# diskohedron4w_revb.net
KiCad netlist of a schematic drawn in EAGLE
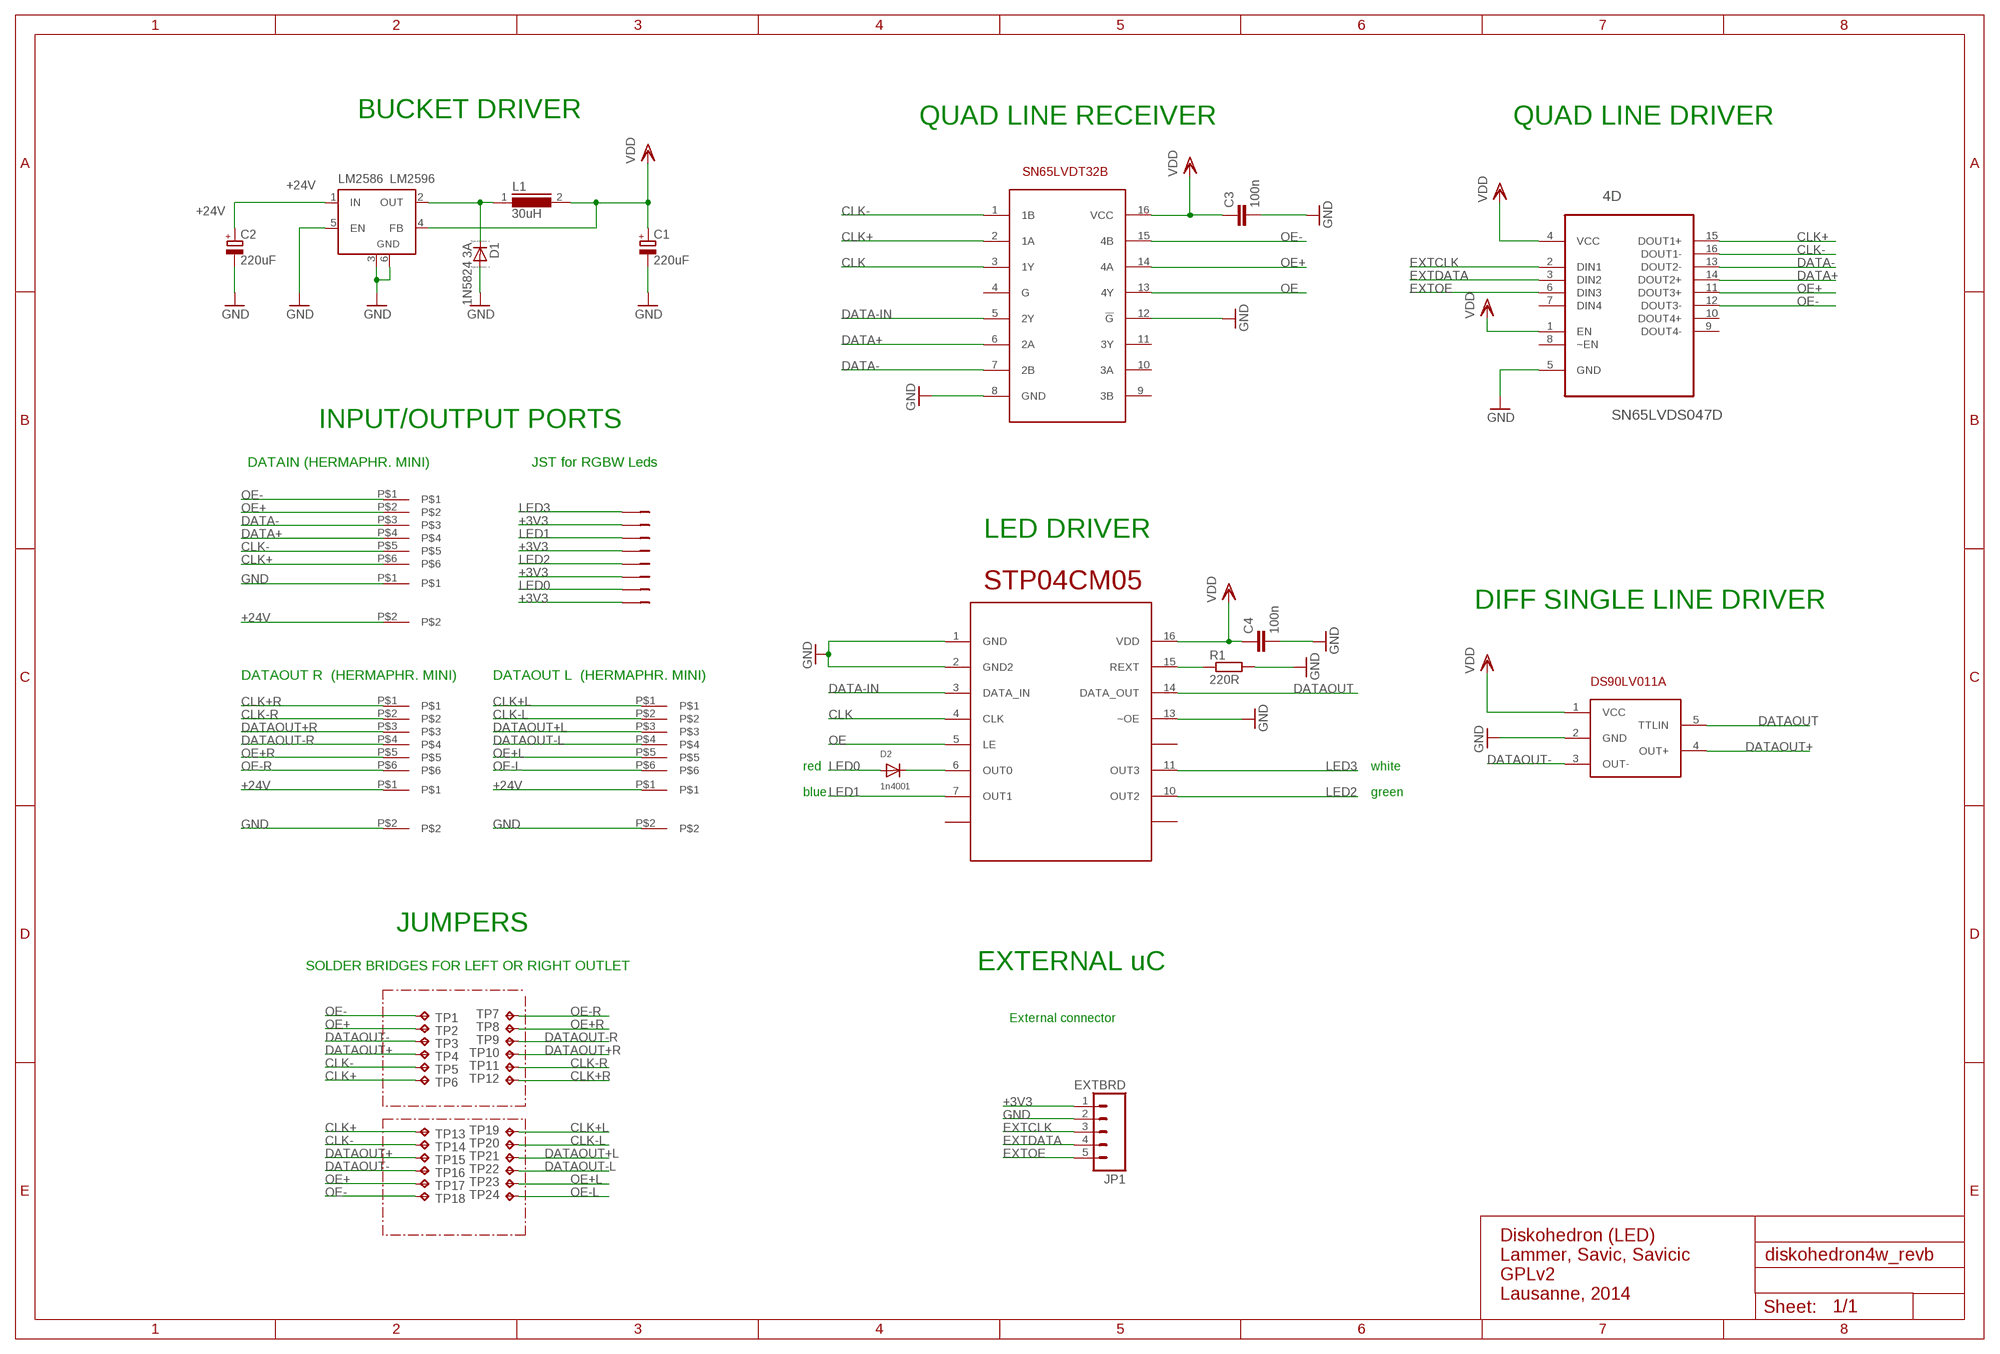
[diagram p0: schematic, sheet 1]

(export (version "E")
  (design (tool "Eeschema 10.0.6"))
  (components
    (comp (ref "1D")
      (value "DS90LV011A")
      (footprint "eagle-import:SOT23-5")
      (libsource (lib "eagle-import") (part "DS90LV011A"))
    )
    (comp (ref "4D")
      (value "SN65LVDS047D")
      (footprint "eagle-import:SOIC127P600X175-16N")
      (libsource (lib "eagle-import") (part "SN65LVDS047D"))
    )
    (comp (ref "4R")
      (value "SN65LVDST32")
      (footprint "eagle-import:SOIC16")
      (libsource (lib "eagle-import") (part "SN65LVDST32"))
    )
    (comp (ref "C1")
      (value "220uF")
      (footprint "eagle-import:175TMP-0810")
      (libsource (lib "eagle-import") (part "CPOL-EU175TMP-0810"))
    )
    (comp (ref "C2")
      (value "220uF")
      (footprint "eagle-import:175TMP-0810")
      (libsource (lib "eagle-import") (part "CPOL-EU175TMP-0810"))
    )
    (comp (ref "C3")
      (value "100n")
      (footprint "eagle-import:C0805")
      (libsource (lib "eagle-import") (part "C-EUC0805"))
    )
    (comp (ref "C4")
      (value "100n")
      (footprint "eagle-import:C0805")
      (libsource (lib "eagle-import") (part "C-EUC0805"))
    )
    (comp (ref "D1")
      (value "1N5824 3A")
      (footprint "eagle-import:DIODE_SMC")
      (libsource (lib "eagle-import") (part "DIODE_E-SMC"))
    )
    (comp (ref "D2")
      (value "1n4001")
      (footprint "eagle-import:SMADIODE")
      (libsource (lib "eagle-import") (part "DIODESMA"))
    )
    (comp (ref "IN1")
      (value "HERMAPHRODITMINI6PIN")
      (footprint "eagle-import:HERMAPHRODITMINI6PIN")
      (libsource (lib "eagle-import") (part "HERMAPHRODITMINI6PIN"))
    )
    (comp (ref "JP1")
      (value "EXTBRD")
      (footprint "eagle-import:1X05")
      (libsource (lib "eagle-import") (part "M05PTH"))
    )
    (comp (ref "JST")
      (value "8PIN-ZH")
      (footprint "eagle-import:B8B-ZH")
      (libsource (lib "eagle-import") (part "8PIN-ZH"))
    )
    (comp (ref "L1")
      (value "30uH")
      (footprint "eagle-import:DR127")
      (libsource (lib "eagle-import") (part "DR127"))
    )
    (comp (ref "LM2586")
      (value "LM2596")
      (footprint "eagle-import:TO263-5")
      (libsource (lib "eagle-import") (part "LM2596S"))
    )
    (comp (ref "OUT-L")
      (value "HERMAPHRODITMINI6PIN")
      (footprint "eagle-import:HERMAPHRODITMINI6PIN")
      (libsource (lib "eagle-import") (part "HERMAPHRODITMINI6PIN"))
    )
    (comp (ref "OUT-R")
      (value "HERMAPHRODITMINI6PIN")
      (footprint "eagle-import:HERMAPHRODITMINI6PIN")
      (libsource (lib "eagle-import") (part "HERMAPHRODITMINI6PIN"))
    )
    (comp (ref "R1")
      (value "220R")
      (footprint "eagle-import:M0805")
      (libsource (lib "eagle-import") (part "R-EU_M0805"))
    )
    (comp (ref "STP04")
      (value "STP04CM05")
      (footprint "eagle-import:TSSOP16")
      (libsource (lib "eagle-import") (part "STP04CM05"))
    )
    (comp (ref "TP1")
      (value "TPTP12SQ")
      (footprint "eagle-import:TP12SQ")
      (libsource (lib "eagle-import") (part "TPTP12SQ"))
    )
    (comp (ref "TP2")
      (value "TPTP12SQ")
      (footprint "eagle-import:TP12SQ")
      (libsource (lib "eagle-import") (part "TPTP12SQ"))
    )
    (comp (ref "TP3")
      (value "TPTP12SQ")
      (footprint "eagle-import:TP12SQ")
      (libsource (lib "eagle-import") (part "TPTP12SQ"))
    )
    (comp (ref "TP4")
      (value "TPTP12SQ")
      (footprint "eagle-import:TP12SQ")
      (libsource (lib "eagle-import") (part "TPTP12SQ"))
    )
    (comp (ref "TP5")
      (value "TPTP12SQ")
      (footprint "eagle-import:TP12SQ")
      (libsource (lib "eagle-import") (part "TPTP12SQ"))
    )
    (comp (ref "TP6")
      (value "TPTP12SQ")
      (footprint "eagle-import:TP12SQ")
      (libsource (lib "eagle-import") (part "TPTP12SQ"))
    )
    (comp (ref "TP7")
      (value "TPTP12SQ")
      (footprint "eagle-import:TP12SQ")
      (libsource (lib "eagle-import") (part "TPTP12SQ"))
    )
    (comp (ref "TP8")
      (value "TPTP12SQ")
      (footprint "eagle-import:TP12SQ")
      (libsource (lib "eagle-import") (part "TPTP12SQ"))
    )
    (comp (ref "TP9")
      (value "TPTP12SQ")
      (footprint "eagle-import:TP12SQ")
      (libsource (lib "eagle-import") (part "TPTP12SQ"))
    )
    (comp (ref "TP10")
      (value "TPTP12SQ")
      (footprint "eagle-import:TP12SQ")
      (libsource (lib "eagle-import") (part "TPTP12SQ"))
    )
    (comp (ref "TP11")
      (value "TPTP12SQ")
      (footprint "eagle-import:TP12SQ")
      (libsource (lib "eagle-import") (part "TPTP12SQ"))
    )
    (comp (ref "TP12")
      (value "TPTP12SQ")
      (footprint "eagle-import:TP12SQ")
      (libsource (lib "eagle-import") (part "TPTP12SQ"))
    )
    (comp (ref "TP13")
      (value "TPTP12SQ")
      (footprint "eagle-import:TP12SQ")
      (libsource (lib "eagle-import") (part "TPTP12SQ"))
    )
    (comp (ref "TP14")
      (value "TPTP12SQ")
      (footprint "eagle-import:TP12SQ")
      (libsource (lib "eagle-import") (part "TPTP12SQ"))
    )
    (comp (ref "TP15")
      (value "TPTP12SQ")
      (footprint "eagle-import:TP12SQ")
      (libsource (lib "eagle-import") (part "TPTP12SQ"))
    )
    (comp (ref "TP16")
      (value "TPTP12SQ")
      (footprint "eagle-import:TP12SQ")
      (libsource (lib "eagle-import") (part "TPTP12SQ"))
    )
    (comp (ref "TP17")
      (value "TPTP12SQ")
      (footprint "eagle-import:TP12SQ")
      (libsource (lib "eagle-import") (part "TPTP12SQ"))
    )
    (comp (ref "TP18")
      (value "TPTP12SQ")
      (footprint "eagle-import:TP12SQ")
      (libsource (lib "eagle-import") (part "TPTP12SQ"))
    )
    (comp (ref "TP19")
      (value "TPTP12SQ")
      (footprint "eagle-import:TP12SQ")
      (libsource (lib "eagle-import") (part "TPTP12SQ"))
    )
    (comp (ref "TP20")
      (value "TPTP12SQ")
      (footprint "eagle-import:TP12SQ")
      (libsource (lib "eagle-import") (part "TPTP12SQ"))
    )
    (comp (ref "TP21")
      (value "TPTP12SQ")
      (footprint "eagle-import:TP12SQ")
      (libsource (lib "eagle-import") (part "TPTP12SQ"))
    )
    (comp (ref "TP22")
      (value "TPTP12SQ")
      (footprint "eagle-import:TP12SQ")
      (libsource (lib "eagle-import") (part "TPTP12SQ"))
    )
    (comp (ref "TP23")
      (value "TPTP12SQ")
      (footprint "eagle-import:TP12SQ")
      (libsource (lib "eagle-import") (part "TPTP12SQ"))
    )
    (comp (ref "TP24")
      (value "TPTP12SQ")
      (footprint "eagle-import:TP12SQ")
      (libsource (lib "eagle-import") (part "TPTP12SQ"))
    )
    (comp (ref "U$6")
      (value "HERMAPHRODIT2PIN")
      (footprint "eagle-import:HERMAPHRODIT2PIN")
      (libsource (lib "eagle-import") (part "HERMAPHRODIT2PIN"))
    )
    (comp (ref "U$7")
      (value "HERMAPHRODIT2PIN")
      (footprint "eagle-import:HERMAPHRODIT2PIN")
      (libsource (lib "eagle-import") (part "HERMAPHRODIT2PIN"))
    )
    (comp (ref "U$12")
      (value "HERMAPHRODIT2PIN")
      (footprint "eagle-import:HERMAPHRODIT2PIN")
      (libsource (lib "eagle-import") (part "HERMAPHRODIT2PIN"))
    )
  )
  (nets
    (net (code "1") (name "/+24V") (class "Default")
      (node (ref "C2") (pin "+") (pinfunction "+_+") (pintype "passive"))
      (node (ref "LM2586") (pin "1") (pinfunction "IN_1") (pintype "input"))
      (node (ref "U$12") (pin "P$1") (pinfunction "P$1_P$1") (pintype "bidirectional"))
      (node (ref "U$6") (pin "P$1") (pinfunction "P$1_P$1") (pintype "bidirectional"))
      (node (ref "U$7") (pin "P$2") (pinfunction "P$2_P$2") (pintype "bidirectional"))
    )
    (net (code "2") (name "/CLK") (class "Default")
      (node (ref "4R") (pin "3") (pinfunction "1Y_3") (pintype "bidirectional"))
      (node (ref "STP04") (pin "4") (pinfunction "CLK_4") (pintype "bidirectional"))
    )
    (net (code "3") (name "/CLK+") (class "Default")
      (node (ref "4D") (pin "15") (pinfunction "DOUT1+_15") (pintype "output"))
      (node (ref "4R") (pin "2") (pinfunction "1A_2") (pintype "bidirectional"))
      (node (ref "IN1") (pin "P$6") (pinfunction "P$6_P$6") (pintype "bidirectional"))
      (node (ref "TP13") (pin "TP") (pinfunction "TP_TP") (pintype "input"))
      (node (ref "TP6") (pin "TP") (pinfunction "TP_TP") (pintype "input"))
    )
    (net (code "4") (name "/CLK+L") (class "Default")
      (node (ref "OUT-L") (pin "P$1") (pinfunction "P$1_P$1") (pintype "bidirectional"))
      (node (ref "TP19") (pin "TP") (pinfunction "TP_TP") (pintype "input"))
    )
    (net (code "5") (name "/CLK+R") (class "Default")
      (node (ref "OUT-R") (pin "P$1") (pinfunction "P$1_P$1") (pintype "bidirectional"))
      (node (ref "TP12") (pin "TP") (pinfunction "TP_TP") (pintype "input"))
    )
    (net (code "6") (name "/CLK-") (class "Default")
      (node (ref "4D") (pin "16") (pinfunction "DOUT1-_16") (pintype "output"))
      (node (ref "4R") (pin "1") (pinfunction "1B_1") (pintype "bidirectional"))
      (node (ref "IN1") (pin "P$5") (pinfunction "P$5_P$5") (pintype "bidirectional"))
      (node (ref "TP14") (pin "TP") (pinfunction "TP_TP") (pintype "input"))
      (node (ref "TP5") (pin "TP") (pinfunction "TP_TP") (pintype "input"))
    )
    (net (code "7") (name "/CLK-L") (class "Default")
      (node (ref "OUT-L") (pin "P$2") (pinfunction "P$2_P$2") (pintype "bidirectional"))
      (node (ref "TP20") (pin "TP") (pinfunction "TP_TP") (pintype "input"))
    )
    (net (code "8") (name "/CLK-R") (class "Default")
      (node (ref "OUT-R") (pin "P$2") (pinfunction "P$2_P$2") (pintype "bidirectional"))
      (node (ref "TP11") (pin "TP") (pinfunction "TP_TP") (pintype "input"))
    )
    (net (code "9") (name "/DATA+") (class "Default")
      (node (ref "4D") (pin "14") (pinfunction "DOUT2+_14") (pintype "output"))
      (node (ref "4R") (pin "6") (pinfunction "2A_6") (pintype "bidirectional"))
      (node (ref "IN1") (pin "P$4") (pinfunction "P$4_P$4") (pintype "bidirectional"))
    )
    (net (code "10") (name "/DATA-") (class "Default")
      (node (ref "4D") (pin "13") (pinfunction "DOUT2-_13") (pintype "output"))
      (node (ref "4R") (pin "7") (pinfunction "2B_7") (pintype "bidirectional"))
      (node (ref "IN1") (pin "P$3") (pinfunction "P$3_P$3") (pintype "bidirectional"))
    )
    (net (code "11") (name "/DATA-IN") (class "Default")
      (node (ref "4R") (pin "5") (pinfunction "2Y_5") (pintype "bidirectional"))
      (node (ref "STP04") (pin "3") (pinfunction "DATA_IN_3") (pintype "bidirectional"))
    )
    (net (code "12") (name "/DATAOUT") (class "Default")
      (node (ref "1D") (pin "5") (pinfunction "TTLIN_5") (pintype "bidirectional"))
      (node (ref "STP04") (pin "14") (pinfunction "DATA_OUT_14") (pintype "bidirectional"))
    )
    (net (code "13") (name "/DATAOUT+") (class "Default")
      (node (ref "1D") (pin "4") (pinfunction "OUT+_4") (pintype "bidirectional"))
      (node (ref "TP15") (pin "TP") (pinfunction "TP_TP") (pintype "input"))
      (node (ref "TP4") (pin "TP") (pinfunction "TP_TP") (pintype "input"))
    )
    (net (code "14") (name "/DATAOUT+L") (class "Default")
      (node (ref "OUT-L") (pin "P$3") (pinfunction "P$3_P$3") (pintype "bidirectional"))
      (node (ref "TP21") (pin "TP") (pinfunction "TP_TP") (pintype "input"))
    )
    (net (code "15") (name "/DATAOUT+R") (class "Default")
      (node (ref "OUT-R") (pin "P$3") (pinfunction "P$3_P$3") (pintype "bidirectional"))
      (node (ref "TP10") (pin "TP") (pinfunction "TP_TP") (pintype "input"))
    )
    (net (code "16") (name "/DATAOUT-") (class "Default")
      (node (ref "1D") (pin "3") (pinfunction "OUT-_3") (pintype "bidirectional"))
      (node (ref "TP16") (pin "TP") (pinfunction "TP_TP") (pintype "input"))
      (node (ref "TP3") (pin "TP") (pinfunction "TP_TP") (pintype "input"))
    )
    (net (code "17") (name "/DATAOUT-L") (class "Default")
      (node (ref "OUT-L") (pin "P$4") (pinfunction "P$4_P$4") (pintype "bidirectional"))
      (node (ref "TP22") (pin "TP") (pinfunction "TP_TP") (pintype "input"))
    )
    (net (code "18") (name "/DATAOUT-R") (class "Default")
      (node (ref "OUT-R") (pin "P$4") (pinfunction "P$4_P$4") (pintype "bidirectional"))
      (node (ref "TP9") (pin "TP") (pinfunction "TP_TP") (pintype "input"))
    )
    (net (code "19") (name "/EXTCLK") (class "Default")
      (node (ref "4D") (pin "2") (pinfunction "DIN1_2") (pintype "input"))
      (node (ref "JP1") (pin "3") (pinfunction "3_3") (pintype "passive"))
    )
    (net (code "20") (name "/EXTDATA") (class "Default")
      (node (ref "4D") (pin "3") (pinfunction "DIN2_3") (pintype "input"))
      (node (ref "JP1") (pin "4") (pinfunction "4_4") (pintype "passive"))
    )
    (net (code "21") (name "/EXTOE") (class "Default")
      (node (ref "4D") (pin "6") (pinfunction "DIN3_6") (pintype "input"))
      (node (ref "JP1") (pin "5") (pinfunction "5_5") (pintype "passive"))
    )
    (net (code "22") (name "/LED0") (class "Default")
      (node (ref "D2") (pin "A") (pinfunction "A_A") (pintype "passive"))
      (node (ref "JST") (pin "7") (pinfunction "1_7") (pintype "passive"))
    )
    (net (code "23") (name "/LED1") (class "Default")
      (node (ref "JST") (pin "3") (pinfunction "1_3") (pintype "passive"))
      (node (ref "STP04") (pin "7") (pinfunction "OUT1_7") (pintype "bidirectional"))
    )
    (net (code "24") (name "/LED2") (class "Default")
      (node (ref "JST") (pin "5") (pinfunction "1_5") (pintype "passive"))
      (node (ref "STP04") (pin "10") (pinfunction "OUT2_10") (pintype "bidirectional"))
    )
    (net (code "25") (name "/LED3") (class "Default")
      (node (ref "JST") (pin "1") (pinfunction "1_1") (pintype "passive"))
      (node (ref "STP04") (pin "11") (pinfunction "OUT3_11") (pintype "bidirectional"))
    )
    (net (code "26") (name "/OE") (class "Default")
      (node (ref "4R") (pin "13") (pinfunction "4Y_13") (pintype "bidirectional"))
      (node (ref "STP04") (pin "5") (pinfunction "LE_5") (pintype "bidirectional"))
    )
    (net (code "27") (name "/OE+") (class "Default")
      (node (ref "4D") (pin "11") (pinfunction "DOUT3+_11") (pintype "output"))
      (node (ref "4R") (pin "14") (pinfunction "4A_14") (pintype "bidirectional"))
      (node (ref "IN1") (pin "P$2") (pinfunction "P$2_P$2") (pintype "bidirectional"))
      (node (ref "TP17") (pin "TP") (pinfunction "TP_TP") (pintype "input"))
      (node (ref "TP2") (pin "TP") (pinfunction "TP_TP") (pintype "input"))
    )
    (net (code "28") (name "/OE+L") (class "Default")
      (node (ref "OUT-L") (pin "P$5") (pinfunction "P$5_P$5") (pintype "bidirectional"))
      (node (ref "TP23") (pin "TP") (pinfunction "TP_TP") (pintype "input"))
    )
    (net (code "29") (name "/OE+R") (class "Default")
      (node (ref "OUT-R") (pin "P$5") (pinfunction "P$5_P$5") (pintype "bidirectional"))
      (node (ref "TP8") (pin "TP") (pinfunction "TP_TP") (pintype "input"))
    )
    (net (code "30") (name "/OE-") (class "Default")
      (node (ref "4D") (pin "12") (pinfunction "DOUT3-_12") (pintype "output"))
      (node (ref "4R") (pin "15") (pinfunction "4B_15") (pintype "bidirectional"))
      (node (ref "IN1") (pin "P$1") (pinfunction "P$1_P$1") (pintype "bidirectional"))
      (node (ref "TP1") (pin "TP") (pinfunction "TP_TP") (pintype "input"))
      (node (ref "TP18") (pin "TP") (pinfunction "TP_TP") (pintype "input"))
    )
    (net (code "31") (name "/OE-L") (class "Default")
      (node (ref "OUT-L") (pin "P$6") (pinfunction "P$6_P$6") (pintype "bidirectional"))
      (node (ref "TP24") (pin "TP") (pinfunction "TP_TP") (pintype "input"))
    )
    (net (code "32") (name "/OE-R") (class "Default")
      (node (ref "OUT-R") (pin "P$6") (pinfunction "P$6_P$6") (pintype "bidirectional"))
      (node (ref "TP7") (pin "TP") (pinfunction "TP_TP") (pintype "input"))
    )
    (net (code "33") (name "GND") (class "Default")
      (node (ref "1D") (pin "2") (pinfunction "GND_2") (pintype "bidirectional"))
      (node (ref "4D") (pin "5") (pinfunction "GND_5") (pintype "passive"))
      (node (ref "4R") (pin "12") (pinfunction "~{G}_12") (pintype "bidirectional"))
      (node (ref "4R") (pin "8") (pinfunction "GND_8") (pintype "bidirectional"))
      (node (ref "C1") (pin "-") (pinfunction "-_-") (pintype "passive"))
      (node (ref "C2") (pin "-") (pinfunction "-_-") (pintype "passive"))
      (node (ref "C3") (pin "2") (pinfunction "2_2") (pintype "passive"))
      (node (ref "C4") (pin "2") (pinfunction "2_2") (pintype "passive"))
      (node (ref "D1") (pin "A") (pinfunction "C_A") (pintype "passive"))
      (node (ref "JP1") (pin "2") (pinfunction "2_2") (pintype "passive"))
      (node (ref "LM2586") (pin "3") (pinfunction "GND_3") (pintype "power_in"))
      (node (ref "LM2586") (pin "5") (pinfunction "EN_5") (pintype "input"))
      (node (ref "LM2586") (pin "6") (pinfunction "GND_6") (pintype "power_in"))
      (node (ref "R1") (pin "2") (pinfunction "2_2") (pintype "passive"))
      (node (ref "STP04") (pin "1") (pinfunction "GND_1") (pintype "bidirectional"))
      (node (ref "STP04") (pin "13") (pinfunction "~{OE}_13") (pintype "bidirectional"))
      (node (ref "STP04") (pin "2") (pinfunction "GND2_2") (pintype "bidirectional"))
      (node (ref "U$12") (pin "P$2") (pinfunction "P$2_P$2") (pintype "bidirectional"))
      (node (ref "U$6") (pin "P$2") (pinfunction "P$2_P$2") (pintype "bidirectional"))
      (node (ref "U$7") (pin "P$1") (pinfunction "P$1_P$1") (pintype "bidirectional"))
    )
    (net (code "34") (name "Net-(D1-A)") (class "Default")
      (node (ref "D1") (pin "C") (pinfunction "A_C") (pintype "passive"))
      (node (ref "L1") (pin "1") (pinfunction "1_1") (pintype "passive"))
      (node (ref "LM2586") (pin "2") (pinfunction "OUT_2") (pintype "output"))
    )
    (net (code "35") (name "Net-(STP04-OUT0)") (class "Default")
      (node (ref "D2") (pin "C") (pinfunction "C_C") (pintype "passive"))
      (node (ref "STP04") (pin "6") (pinfunction "OUT0_6") (pintype "bidirectional"))
    )
    (net (code "36") (name "Net-(STP04-REXT)") (class "Default")
      (node (ref "R1") (pin "1") (pinfunction "1_1") (pintype "passive"))
      (node (ref "STP04") (pin "15") (pinfunction "REXT_15") (pintype "bidirectional"))
    )
    (net (code "37") (name "VDD") (class "Default")
      (node (ref "1D") (pin "1") (pinfunction "VCC_1") (pintype "bidirectional"))
      (node (ref "4D") (pin "1") (pinfunction "EN_1") (pintype "input"))
      (node (ref "4D") (pin "4") (pinfunction "VCC_4") (pintype "power_in"))
      (node (ref "4R") (pin "16") (pinfunction "VCC_16") (pintype "bidirectional"))
      (node (ref "C1") (pin "+") (pinfunction "+_+") (pintype "passive"))
      (node (ref "C3") (pin "1") (pinfunction "1_1") (pintype "passive"))
      (node (ref "C4") (pin "1") (pinfunction "1_1") (pintype "passive"))
      (node (ref "JP1") (pin "1") (pinfunction "1_1") (pintype "passive"))
      (node (ref "JST") (pin "2") (pinfunction "1_2") (pintype "passive"))
      (node (ref "JST") (pin "4") (pinfunction "1_4") (pintype "passive"))
      (node (ref "JST") (pin "6") (pinfunction "1_6") (pintype "passive"))
      (node (ref "JST") (pin "8") (pinfunction "1_8") (pintype "passive"))
      (node (ref "L1") (pin "2") (pinfunction "2_2") (pintype "passive"))
      (node (ref "LM2586") (pin "4") (pinfunction "FB_4") (pintype "input"))
      (node (ref "STP04") (pin "16") (pinfunction "VDD_16") (pintype "bidirectional"))
    )
    (net (code "38") (name "unconnected-(4D-DIN4-Pad7)") (class "Default")
      (node (ref "4D") (pin "7") (pinfunction "DIN4_7") (pintype "input"))
    )
    (net (code "39") (name "unconnected-(4D-DOUT4+-Pad10)") (class "Default")
      (node (ref "4D") (pin "10") (pinfunction "DOUT4+_10") (pintype "output"))
    )
    (net (code "40") (name "unconnected-(4D-DOUT4--Pad9)") (class "Default")
      (node (ref "4D") (pin "9") (pinfunction "DOUT4-_9") (pintype "output"))
    )
    (net (code "41") (name "unconnected-(4D-~{EN}-Pad8)") (class "Default")
      (node (ref "4D") (pin "8") (pinfunction "~{EN}_8") (pintype "input"))
    )
    (net (code "42") (name "unconnected-(4R-3A-Pad10)") (class "Default")
      (node (ref "4R") (pin "10") (pinfunction "3A_10") (pintype "bidirectional"))
    )
    (net (code "43") (name "unconnected-(4R-3B-Pad9)") (class "Default")
      (node (ref "4R") (pin "9") (pinfunction "3B_9") (pintype "bidirectional"))
    )
    (net (code "44") (name "unconnected-(4R-3Y-Pad11)") (class "Default")
      (node (ref "4R") (pin "11") (pinfunction "3Y_11") (pintype "bidirectional"))
    )
    (net (code "45") (name "unconnected-(4R-G-Pad4)") (class "Default")
      (node (ref "4R") (pin "4") (pinfunction "G_4") (pintype "bidirectional"))
    )
    (net (code "46") (name "unconnected-(STP04-N.C1-Pad8)") (class "Default")
      (node (ref "STP04") (pin "8") (pinfunction "N.C1_8") (pintype "bidirectional"))
    )
    (net (code "47") (name "unconnected-(STP04-NC-Pad9)") (class "Default")
      (node (ref "STP04") (pin "9") (pinfunction "NC_9") (pintype "bidirectional"))
    )
    (net (code "48") (name "unconnected-(STP04-NC3-Pad12)") (class "Default")
      (node (ref "STP04") (pin "12") (pinfunction "NC3_12") (pintype "bidirectional"))
    )
  )
)
